# vezerlo_V2.net
KiCad netlist of a schematic drawn in EAGLE
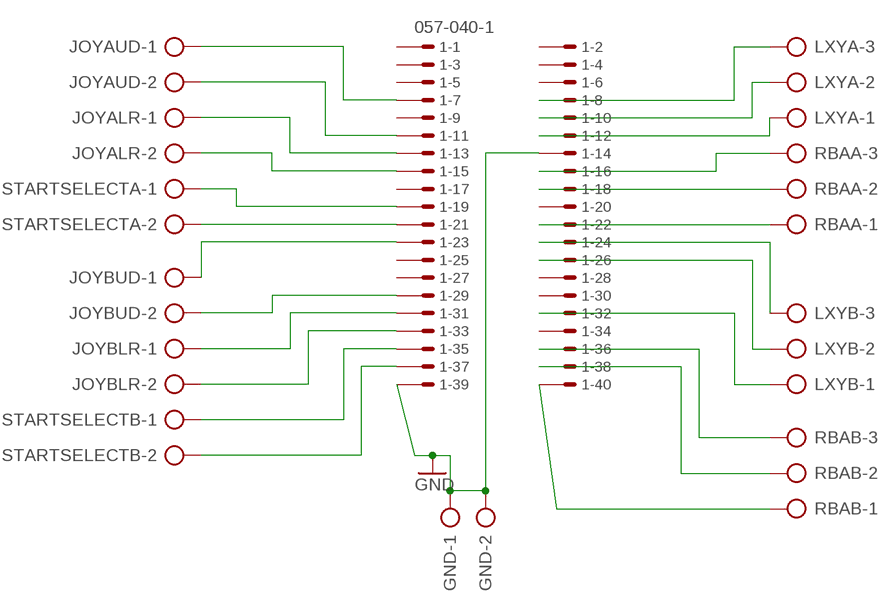
[diagram p0: schematic, sheet 1]

(export (version "E")
  (design (tool "Eeschema 10.0.6"))
  (components
    (comp (ref "1")
      (value "057-040-1")
      (footprint "eagle-import:057-040-1")
      (libsource (lib "eagle-import") (part "057-040-1"))
    )
    (comp (ref "GND")
      (value "AK500/2-H")
      (footprint "eagle-import:AK500_2-H")
      (libsource (lib "eagle-import") (part "AK500/2-H"))
    )
    (comp (ref "JOYALR")
      (value "AK500/2-H")
      (footprint "eagle-import:AK500_2-H")
      (libsource (lib "eagle-import") (part "AK500/2-H"))
    )
    (comp (ref "JOYAUD")
      (value "AK500/2-H")
      (footprint "eagle-import:AK500_2-H")
      (libsource (lib "eagle-import") (part "AK500/2-H"))
    )
    (comp (ref "JOYBLR")
      (value "AK500/2-H")
      (footprint "eagle-import:AK500_2-H")
      (libsource (lib "eagle-import") (part "AK500/2-H"))
    )
    (comp (ref "JOYBUD")
      (value "AK500/2-H")
      (footprint "eagle-import:AK500_2-H")
      (libsource (lib "eagle-import") (part "AK500/2-H"))
    )
    (comp (ref "LXYA")
      (value "AK500/3-H")
      (footprint "eagle-import:AK500_3-H")
      (libsource (lib "eagle-import") (part "AK500/3-H"))
    )
    (comp (ref "LXYB")
      (value "AK500/3-H")
      (footprint "eagle-import:AK500_3-H")
      (libsource (lib "eagle-import") (part "AK500/3-H"))
    )
    (comp (ref "RBAA")
      (value "AK500/3-H")
      (footprint "eagle-import:AK500_3-H")
      (libsource (lib "eagle-import") (part "AK500/3-H"))
    )
    (comp (ref "RBAB")
      (value "AK500/3-H")
      (footprint "eagle-import:AK500_3-H")
      (libsource (lib "eagle-import") (part "AK500/3-H"))
    )
    (comp (ref "STARTSELECTA")
      (value "AK500/2-H")
      (footprint "eagle-import:AK500_2-H")
      (libsource (lib "eagle-import") (part "AK500/2-H"))
    )
    (comp (ref "STARTSELECTB")
      (value "AK500/2-H")
      (footprint "eagle-import:AK500_2-H")
      (libsource (lib "eagle-import") (part "AK500/2-H"))
    )
  )
  (nets
    (net (code "1") (name "GND") (class "Default")
      (node (ref "1") (pin "14") (pinfunction "S_14") (pintype "passive"))
      (node (ref "1") (pin "39") (pinfunction "S_39") (pintype "passive"))
      (node (ref "GND") (pin "1") (pinfunction "KL_1") (pintype "passive"))
      (node (ref "GND") (pin "2") (pinfunction "KL_2") (pintype "passive"))
    )
    (net (code "2") (name "Net-(1AA-S)") (class "Default")
      (node (ref "1") (pin "33") (pinfunction "S_33") (pintype "passive"))
      (node (ref "JOYBLR") (pin "2") (pinfunction "KL_2") (pintype "passive"))
    )
    (net (code "3") (name "Net-(1AC-S)") (class "Default")
      (node (ref "1") (pin "35") (pinfunction "S_35") (pintype "passive"))
      (node (ref "STARTSELECTB") (pin "1") (pinfunction "KL_1") (pintype "passive"))
    )
    (net (code "4") (name "Net-(1AD-S)") (class "Default")
      (node (ref "1") (pin "36") (pinfunction "S_36") (pintype "passive"))
      (node (ref "RBAB") (pin "3") (pinfunction "KL_3") (pintype "passive"))
    )
    (net (code "5") (name "Net-(1AE-S)") (class "Default")
      (node (ref "1") (pin "37") (pinfunction "S_37") (pintype "passive"))
      (node (ref "STARTSELECTB") (pin "2") (pinfunction "KL_2") (pintype "passive"))
    )
    (net (code "6") (name "Net-(1AF-S)") (class "Default")
      (node (ref "1") (pin "38") (pinfunction "S_38") (pintype "passive"))
      (node (ref "RBAB") (pin "2") (pinfunction "KL_2") (pintype "passive"))
    )
    (net (code "7") (name "Net-(1AI-S)") (class "Default")
      (node (ref "1") (pin "40") (pinfunction "S_40") (pintype "passive"))
      (node (ref "RBAB") (pin "1") (pinfunction "KL_1") (pintype "passive"))
    )
    (net (code "8") (name "Net-(1AL-S)") (class "Default")
      (node (ref "1") (pin "7") (pinfunction "S_7") (pintype "passive"))
      (node (ref "JOYAUD") (pin "1") (pinfunction "KL_1") (pintype "passive"))
    )
    (net (code "9") (name "Net-(1AM-S)") (class "Default")
      (node (ref "1") (pin "8") (pinfunction "S_8") (pintype "passive"))
      (node (ref "LXYA") (pin "3") (pinfunction "KL_3") (pintype "passive"))
    )
    (net (code "10") (name "Net-(1B-S)") (class "Default")
      (node (ref "1") (pin "10") (pinfunction "S_10") (pintype "passive"))
      (node (ref "LXYA") (pin "2") (pinfunction "KL_2") (pintype "passive"))
    )
    (net (code "11") (name "Net-(1C-S)") (class "Default")
      (node (ref "1") (pin "11") (pinfunction "S_11") (pintype "passive"))
      (node (ref "JOYAUD") (pin "2") (pinfunction "KL_2") (pintype "passive"))
    )
    (net (code "12") (name "Net-(1D-S)") (class "Default")
      (node (ref "1") (pin "12") (pinfunction "S_12") (pintype "passive"))
      (node (ref "LXYA") (pin "1") (pinfunction "KL_1") (pintype "passive"))
    )
    (net (code "13") (name "Net-(1E-S)") (class "Default")
      (node (ref "1") (pin "13") (pinfunction "S_13") (pintype "passive"))
      (node (ref "JOYALR") (pin "1") (pinfunction "KL_1") (pintype "passive"))
    )
    (net (code "14") (name "Net-(1G-S)") (class "Default")
      (node (ref "1") (pin "15") (pinfunction "S_15") (pintype "passive"))
      (node (ref "JOYALR") (pin "2") (pinfunction "KL_2") (pintype "passive"))
    )
    (net (code "15") (name "Net-(1H-S)") (class "Default")
      (node (ref "1") (pin "16") (pinfunction "S_16") (pintype "passive"))
      (node (ref "RBAA") (pin "3") (pinfunction "KL_3") (pintype "passive"))
    )
    (net (code "16") (name "Net-(1J-S)") (class "Default")
      (node (ref "1") (pin "18") (pinfunction "S_18") (pintype "passive"))
      (node (ref "RBAA") (pin "2") (pinfunction "KL_2") (pintype "passive"))
    )
    (net (code "17") (name "Net-(1K-S)") (class "Default")
      (node (ref "1") (pin "19") (pinfunction "S_19") (pintype "passive"))
      (node (ref "STARTSELECTA") (pin "1") (pinfunction "KL_1") (pintype "passive"))
    )
    (net (code "18") (name "Net-(1N-S)") (class "Default")
      (node (ref "1") (pin "21") (pinfunction "S_21") (pintype "passive"))
      (node (ref "STARTSELECTA") (pin "2") (pinfunction "KL_2") (pintype "passive"))
    )
    (net (code "19") (name "Net-(1O-S)") (class "Default")
      (node (ref "1") (pin "22") (pinfunction "S_22") (pintype "passive"))
      (node (ref "RBAA") (pin "1") (pinfunction "KL_1") (pintype "passive"))
    )
    (net (code "20") (name "Net-(1P-S)") (class "Default")
      (node (ref "1") (pin "23") (pinfunction "S_23") (pintype "passive"))
      (node (ref "JOYBUD") (pin "1") (pinfunction "KL_1") (pintype "passive"))
    )
    (net (code "21") (name "Net-(1Q-S)") (class "Default")
      (node (ref "1") (pin "24") (pinfunction "S_24") (pintype "passive"))
      (node (ref "LXYB") (pin "3") (pinfunction "KL_3") (pintype "passive"))
    )
    (net (code "22") (name "Net-(1S-S)") (class "Default")
      (node (ref "1") (pin "26") (pinfunction "S_26") (pintype "passive"))
      (node (ref "LXYB") (pin "2") (pinfunction "KL_2") (pintype "passive"))
    )
    (net (code "23") (name "Net-(1V-S)") (class "Default")
      (node (ref "1") (pin "29") (pinfunction "S_29") (pintype "passive"))
      (node (ref "JOYBUD") (pin "2") (pinfunction "KL_2") (pintype "passive"))
    )
    (net (code "24") (name "Net-(1Y-S)") (class "Default")
      (node (ref "1") (pin "31") (pinfunction "S_31") (pintype "passive"))
      (node (ref "JOYBLR") (pin "1") (pinfunction "KL_1") (pintype "passive"))
    )
    (net (code "25") (name "Net-(1Z-S)") (class "Default")
      (node (ref "1") (pin "32") (pinfunction "S_32") (pintype "passive"))
      (node (ref "LXYB") (pin "1") (pinfunction "KL_1") (pintype "passive"))
    )
    (net (code "26") (name "unconnected-(1A-S-Pad1)") (class "Default")
      (node (ref "1") (pin "1") (pinfunction "S_1") (pintype "passive"))
    )
    (net (code "27") (name "unconnected-(1AB-S-Pad34)") (class "Default")
      (node (ref "1") (pin "34") (pinfunction "S_34") (pintype "passive"))
    )
    (net (code "28") (name "unconnected-(1AH-S-Pad4)") (class "Default")
      (node (ref "1") (pin "4") (pinfunction "S_4") (pintype "passive"))
    )
    (net (code "29") (name "unconnected-(1AJ-S-Pad5)") (class "Default")
      (node (ref "1") (pin "5") (pinfunction "S_5") (pintype "passive"))
    )
    (net (code "30") (name "unconnected-(1AK-S-Pad6)") (class "Default")
      (node (ref "1") (pin "6") (pinfunction "S_6") (pintype "passive"))
    )
    (net (code "31") (name "unconnected-(1AN-S-Pad9)") (class "Default")
      (node (ref "1") (pin "9") (pinfunction "S_9") (pintype "passive"))
    )
    (net (code "32") (name "unconnected-(1I-S-Pad17)") (class "Default")
      (node (ref "1") (pin "17") (pinfunction "S_17") (pintype "passive"))
    )
    (net (code "33") (name "unconnected-(1L-S-Pad2)") (class "Default")
      (node (ref "1") (pin "2") (pinfunction "S_2") (pintype "passive"))
    )
    (net (code "34") (name "unconnected-(1M-S-Pad20)") (class "Default")
      (node (ref "1") (pin "20") (pinfunction "S_20") (pintype "passive"))
    )
    (net (code "35") (name "unconnected-(1R-S-Pad25)") (class "Default")
      (node (ref "1") (pin "25") (pinfunction "S_25") (pintype "passive"))
    )
    (net (code "36") (name "unconnected-(1T-S-Pad27)") (class "Default")
      (node (ref "1") (pin "27") (pinfunction "S_27") (pintype "passive"))
    )
    (net (code "37") (name "unconnected-(1U-S-Pad28)") (class "Default")
      (node (ref "1") (pin "28") (pinfunction "S_28") (pintype "passive"))
    )
    (net (code "38") (name "unconnected-(1W-S-Pad3)") (class "Default")
      (node (ref "1") (pin "3") (pinfunction "S_3") (pintype "passive"))
    )
    (net (code "39") (name "unconnected-(1X-S-Pad30)") (class "Default")
      (node (ref "1") (pin "30") (pinfunction "S_30") (pintype "passive"))
    )
  )
)
